# FPGA_Config.net
KiCad netlist of a schematic drawn in Altium Designer
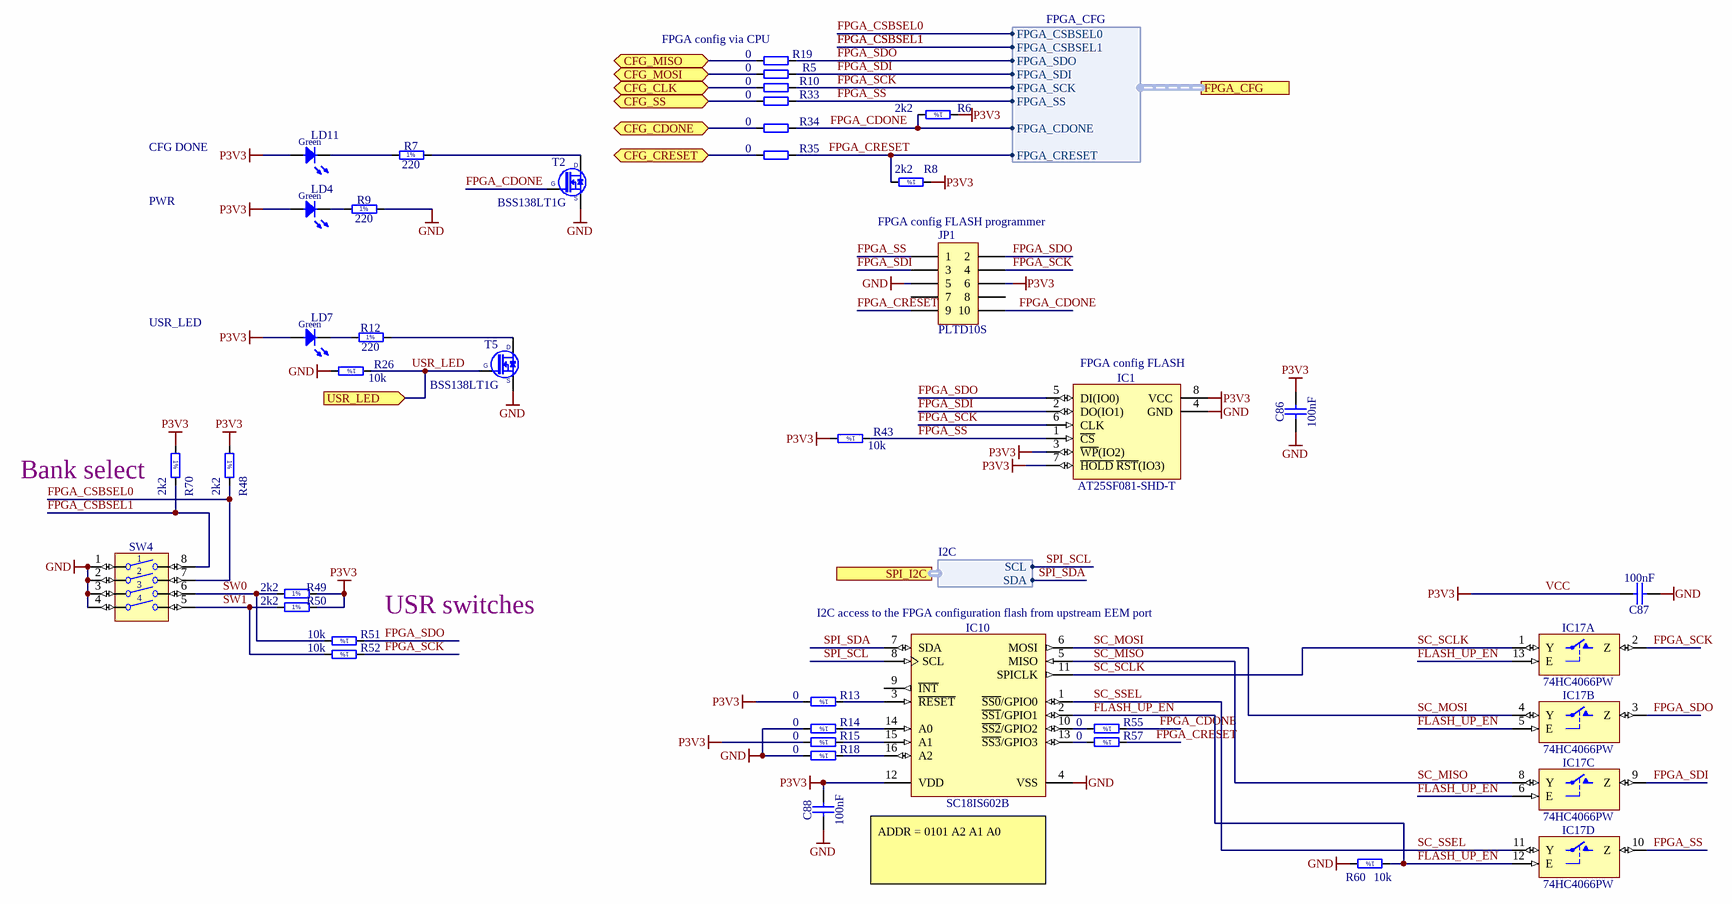
[diagram p0: FPGA_Config.SchDoc]

(export (version "E")
  (design (tool "Eeschema 10.0.6"))
  (components
    (comp (ref "C86")
      (value "100nF")
      (footprint "CAPC1005X55N")
      (description "Non-polarised capacitor")
      (fields
        (field (name "PART NUMBER") "CC0402_100NF_16V_10%_X5R")
        (field (name "VOLTAGE") "16V")
        (field (name "AUTHOR") "CERN DEM JLC")
      )
      (libsource (lib "Capacitors") (part "Capacitor - non polarized"))
    )
    (comp (ref "C87")
      (value "100nF")
      (footprint "CAPC1005X55N")
      (description "Non-polarised capacitor")
      (fields
        (field (name "PART NUMBER") "CC0402_100NF_16V_10%_X5R")
        (field (name "VOLTAGE") "16V")
        (field (name "AUTHOR") "CERN DEM JLC")
      )
      (libsource (lib "Capacitors") (part "Capacitor - non polarized"))
    )
    (comp (ref "C88")
      (value "100nF")
      (footprint "CAPC1005X55N")
      (description "Non-polarised capacitor")
      (fields
        (field (name "PART NUMBER") "CC0402_100NF_16V_10%_X5R")
        (field (name "VOLTAGE") "16V")
        (field (name "AUTHOR") "CERN DEM JLC")
      )
      (libsource (lib "Capacitors") (part "Capacitor - non polarized"))
    )
    (comp (ref "IC1")
      (value "AT25SF081-SHD-T")
      (footprint "SOIC127P790X216-8N")
      (description "8M-bit Serial Flash Memory with uniform 4KB sectors and Dual/Quad SPI and QPI")
      (fields (field (name "MANUFACTURER") "ADESTO") (field (name "AUTHOR") "GK"))
      (libsource (lib "LIBRARY_SCH") (part "MEM_AT25SF081-SHD-T"))
    )
    (comp (ref "IC10")
      (value "SC18IS602B")
      (footprint "SOP65P640X110-16N")
      (description "I2C-bus to SPI bridge")
      (fields (field (name "MANUFACTURER") "NXP SEMICONDUCTORS") (field (name "AUTHOR") "CERN DEM MR"))
      (libsource (lib "ICs And Semiconductors") (part "SC18IS602B"))
    )
    (comp (ref "IC17")
      (value "74HC4066PW")
      (footprint "SOP65P640X110-14N")
      (fields (field (name "MANUFACTURER") "NXP SEMICONDUCTORS") (field (name "AUTHOR") "CERN DEM JLC"))
      (libsource (lib "ICs And Semiconductors") (part "4066"))
    )
    (comp (ref "JP1")
      (value "PLTD10S")
      (footprint "PLTD10S")
      (description "Goldpin 2.54mm, male header")
      (libsource (lib "LIBRARY_SCH") (part "CON_2x5 2.54 male SMT"))
    )
    (comp (ref "LD4")
      (value "Green")
      (footprint "LED_AVAGO_HSME-C120")
      (description "LED Green 1C 2A")
      (fields
        (field (name "PART NUMBER") "LED_AVAGO_HSME-C120")
        (field (name "MANUFACTURER") "AVAGO TECHNOLOGIES")
        (field (name "AUTHOR") "CERN DEM JMW")
      )
      (libsource (lib "ICs And Semiconductors") (part "LED Green 1C 2A"))
    )
    (comp (ref "LD7")
      (value "Green")
      (footprint "LED_AVAGO_HSME-C120")
      (description "LED Green 1C 2A")
      (fields
        (field (name "PART NUMBER") "LED_AVAGO_HSME-C120")
        (field (name "MANUFACTURER") "AVAGO TECHNOLOGIES")
        (field (name "AUTHOR") "CERN DEM JMW")
      )
      (libsource (lib "ICs And Semiconductors") (part "LED Green 1C 2A"))
    )
    (comp (ref "LD11")
      (value "Green")
      (footprint "LED_AVAGO_HSME-C120")
      (description "LED Green 1C 2A")
      (fields
        (field (name "PART NUMBER") "LED_AVAGO_HSME-C120")
        (field (name "MANUFACTURER") "AVAGO TECHNOLOGIES")
        (field (name "AUTHOR") "CERN DEM JMW")
      )
      (libsource (lib "ICs And Semiconductors") (part "LED Green 1C 2A"))
    )
    (comp (ref "R5")
      (value "0")
      (footprint "RESC1608X55N")
      (description "Resistor")
      (fields
        (field (name "PART NUMBER") "R0603_0R_JUMPER")
        (field (name "MANUFACTURER") "GENERIC")
        (field (name "AUTHOR") "CERN DEM JLC")
      )
      (libsource (lib "Resistors") (part "Resistor"))
    )
    (comp (ref "R6")
      (value "2k2")
      (footprint "RESC1005X40N")
      (description "Resistor - 1%")
      (fields
        (field (name "PART NUMBER") "R0402_2K2_1%_0.0625W_100PPM")
        (field (name "POWER") "0.0625W")
        (field (name "AUTHOR") "CERN DEM JLC")
      )
      (libsource (lib "Resistors") (part "Resistor - 1%"))
    )
    (comp (ref "R7")
      (value "220")
      (footprint "RESC1608X55N")
      (description "Resistor - 1%")
      (fields
        (field (name "PART NUMBER") "R0603_220R_1%_0.1W_100PPM")
        (field (name "POWER") "0.1W")
        (field (name "AUTHOR") "CERN DEM JLC")
      )
      (libsource (lib "Resistors") (part "Resistor - 1%"))
    )
    (comp (ref "R8")
      (value "2k2")
      (footprint "RESC1005X40N")
      (description "Resistor - 1%")
      (fields
        (field (name "PART NUMBER") "R0402_2K2_1%_0.0625W_100PPM")
        (field (name "POWER") "0.0625W")
        (field (name "AUTHOR") "CERN DEM JLC")
      )
      (libsource (lib "Resistors") (part "Resistor - 1%"))
    )
    (comp (ref "R9")
      (value "220")
      (footprint "RESC1608X55N")
      (description "Resistor - 1%")
      (fields
        (field (name "PART NUMBER") "R0603_220R_1%_0.1W_100PPM")
        (field (name "POWER") "0.1W")
        (field (name "AUTHOR") "CERN DEM JLC")
      )
      (libsource (lib "Resistors") (part "Resistor - 1%"))
    )
    (comp (ref "R10")
      (value "0")
      (footprint "RESC1608X55N")
      (description "Resistor")
      (fields
        (field (name "PART NUMBER") "R0603_0R_JUMPER")
        (field (name "MANUFACTURER") "GENERIC")
        (field (name "AUTHOR") "CERN DEM JLC")
      )
      (libsource (lib "Resistors") (part "Resistor"))
    )
    (comp (ref "R12")
      (value "220")
      (footprint "RESC1608X55N")
      (description "Resistor - 1%")
      (fields
        (field (name "PART NUMBER") "R0603_220R_1%_0.1W_100PPM")
        (field (name "POWER") "0.1W")
        (field (name "AUTHOR") "CERN DEM JLC")
      )
      (libsource (lib "Resistors") (part "Resistor - 1%"))
    )
    (comp (ref "R13")
      (value "0")
      (footprint "RESC1608X55N")
      (description "Resistor - 1%")
      (fields
        (field (name "PART NUMBER") "R0603_0R_JUMPER")
        (field (name "MANUFACTURER") "GENERIC")
        (field (name "AUTHOR") "CERN DEM JLC")
      )
      (libsource (lib "Resistors") (part "Resistor - 1%"))
    )
    (comp (ref "R14")
      (value "0")
      (footprint "RESC1608X55N")
      (description "Resistor - 1%")
      (fields
        (field (name "PART NUMBER") "R0603_0R_JUMPER")
        (field (name "MANUFACTURER") "GENERIC")
        (field (name "AUTHOR") "CERN DEM JLC")
      )
      (libsource (lib "Resistors") (part "Resistor - 1%"))
    )
    (comp (ref "R15")
      (value "0")
      (footprint "RESC1608X55N")
      (description "Resistor - 1%")
      (fields
        (field (name "PART NUMBER") "R0603_0R_JUMPER")
        (field (name "MANUFACTURER") "GENERIC")
        (field (name "AUTHOR") "CERN DEM JLC")
      )
      (libsource (lib "Resistors") (part "Resistor - 1%"))
    )
    (comp (ref "R18")
      (value "0")
      (footprint "RESC1608X55N")
      (description "Resistor - 1%")
      (fields
        (field (name "PART NUMBER") "R0603_0R_JUMPER")
        (field (name "MANUFACTURER") "GENERIC")
        (field (name "AUTHOR") "CERN DEM JLC")
      )
      (libsource (lib "Resistors") (part "Resistor - 1%"))
    )
    (comp (ref "R19")
      (value "0")
      (footprint "RESC1608X55N")
      (description "Resistor")
      (fields
        (field (name "PART NUMBER") "R0603_0R_JUMPER")
        (field (name "MANUFACTURER") "GENERIC")
        (field (name "AUTHOR") "CERN DEM JLC")
      )
      (libsource (lib "Resistors") (part "Resistor"))
    )
    (comp (ref "R26")
      (value "10k")
      (footprint "RESC1005X40N")
      (description "Resistor - 1%")
      (fields
        (field (name "PART NUMBER") "R0402_10K_1%_0.0625W_100PPM")
        (field (name "POWER") "0.0625W")
        (field (name "AUTHOR") "CERN DEM JLC")
      )
      (libsource (lib "Resistors") (part "Resistor - 1%"))
    )
    (comp (ref "R33")
      (value "0")
      (footprint "RESC1608X55N")
      (description "Resistor")
      (fields
        (field (name "PART NUMBER") "R0603_0R_JUMPER")
        (field (name "MANUFACTURER") "GENERIC")
        (field (name "AUTHOR") "CERN DEM JLC")
      )
      (libsource (lib "Resistors") (part "Resistor"))
    )
    (comp (ref "R34")
      (value "0")
      (footprint "RESC1608X55N")
      (description "Resistor")
      (fields
        (field (name "PART NUMBER") "R0603_0R_JUMPER")
        (field (name "MANUFACTURER") "GENERIC")
        (field (name "AUTHOR") "CERN DEM JLC")
      )
      (libsource (lib "Resistors") (part "Resistor"))
    )
    (comp (ref "R35")
      (value "0")
      (footprint "RESC1608X55N")
      (description "Resistor")
      (fields
        (field (name "PART NUMBER") "R0603_0R_JUMPER")
        (field (name "MANUFACTURER") "GENERIC")
        (field (name "AUTHOR") "CERN DEM JLC")
      )
      (libsource (lib "Resistors") (part "Resistor"))
    )
    (comp (ref "R43")
      (value "10k")
      (footprint "RESC1005X40N")
      (description "Resistor - 1%")
      (fields
        (field (name "PART NUMBER") "R0402_10K_1%_0.0625W_100PPM")
        (field (name "POWER") "0.0625W")
        (field (name "AUTHOR") "CERN DEM JLC")
      )
      (libsource (lib "Resistors") (part "Resistor - 1%"))
    )
    (comp (ref "R48")
      (value "2k2")
      (footprint "RESC1005X40N")
      (description "Resistor - 1%")
      (fields
        (field (name "PART NUMBER") "R0402_2K2_1%_0.0625W_100PPM")
        (field (name "POWER") "0.0625W")
        (field (name "AUTHOR") "CERN DEM JLC")
      )
      (libsource (lib "Resistors") (part "Resistor - 1%"))
    )
    (comp (ref "R49")
      (value "2k2")
      (footprint "RESC1005X40N")
      (description "Resistor - 1%")
      (fields
        (field (name "PART NUMBER") "R0402_2K2_1%_0.0625W_100PPM")
        (field (name "POWER") "0.0625W")
        (field (name "AUTHOR") "CERN DEM JLC")
      )
      (libsource (lib "Resistors") (part "Resistor - 1%"))
    )
    (comp (ref "R50")
      (value "2k2")
      (footprint "RESC1005X40N")
      (description "Resistor - 1%")
      (fields
        (field (name "PART NUMBER") "R0402_2K2_1%_0.0625W_100PPM")
        (field (name "POWER") "0.0625W")
        (field (name "AUTHOR") "CERN DEM JLC")
      )
      (libsource (lib "Resistors") (part "Resistor - 1%"))
    )
    (comp (ref "R51")
      (value "10k")
      (footprint "RESC1005X40N")
      (description "Resistor - 1%")
      (fields
        (field (name "PART NUMBER") "R0402_10K_1%_0.0625W_100PPM")
        (field (name "POWER") "0.0625W")
        (field (name "AUTHOR") "CERN DEM JLC")
      )
      (libsource (lib "Resistors") (part "Resistor - 1%"))
    )
    (comp (ref "R52")
      (value "10k")
      (footprint "RESC1005X40N")
      (description "Resistor - 1%")
      (fields
        (field (name "PART NUMBER") "R0402_10K_1%_0.0625W_100PPM")
        (field (name "POWER") "0.0625W")
        (field (name "AUTHOR") "CERN DEM JLC")
      )
      (libsource (lib "Resistors") (part "Resistor - 1%"))
    )
    (comp (ref "R55")
      (value "0")
      (footprint "RESC1608X55N")
      (description "Resistor - 1%")
      (fields
        (field (name "PART NUMBER") "R0603_0R_JUMPER")
        (field (name "MANUFACTURER") "GENERIC")
        (field (name "AUTHOR") "CERN DEM JLC")
      )
      (libsource (lib "Resistors") (part "Resistor - 1%"))
    )
    (comp (ref "R57")
      (value "0")
      (footprint "RESC1608X55N")
      (description "Resistor - 1%")
      (fields
        (field (name "PART NUMBER") "R0603_0R_JUMPER")
        (field (name "MANUFACTURER") "GENERIC")
        (field (name "AUTHOR") "CERN DEM JLC")
      )
      (libsource (lib "Resistors") (part "Resistor - 1%"))
    )
    (comp (ref "R60")
      (value "10k")
      (footprint "RESC1005X40N")
      (description "Resistor - 1%")
      (fields
        (field (name "PART NUMBER") "R0402_10K_1%_0.0625W_100PPM")
        (field (name "POWER") "0.0625W")
        (field (name "AUTHOR") "CERN DEM JLC")
      )
      (libsource (lib "Resistors") (part "Resistor - 1%"))
    )
    (comp (ref "R70")
      (value "2k2")
      (footprint "RESC1005X40N")
      (description "Resistor - 1%")
      (fields
        (field (name "PART NUMBER") "R0402_2K2_1%_0.0625W_100PPM")
        (field (name "POWER") "0.0625W")
        (field (name "AUTHOR") "CERN DEM JLC")
      )
      (libsource (lib "Resistors") (part "Resistor - 1%"))
    )
    (comp (ref "SW4")
      (value "Switch")
      (footprint "SW_TYCO_1571983-4")
      (description "4 Ways SPST DIP Switch")
      (fields
        (field (name "PART NUMBER") "SW_TYCO_1571983-4")
        (field (name "MANUFACTURER") "TYCO")
        (field (name "AUTHOR") "CERN DEM JLC")
      )
      (libsource (lib "Eletro-mechanical") (part "SW 4x SPST DIP Switch"))
    )
    (comp (ref "T2")
      (value "BSS138LT1G")
      (footprint "SOT95P240X110-3N")
      (description "N-CHANNEL MOSFET WITH DIODE")
      (fields (field (name "MANUFACTURER") "ON SEMICONDUCTOR") (field (name "AUTHOR") "CERN DEM JLC"))
      (libsource (lib "ICs And Semiconductors") (part "N-MOSFET-D 1G 2S 3D"))
    )
    (comp (ref "T5")
      (value "BSS138LT1G")
      (footprint "SOT95P240X110-3N")
      (description "N-CHANNEL MOSFET WITH DIODE")
      (fields (field (name "MANUFACTURER") "ON SEMICONDUCTOR") (field (name "AUTHOR") "CERN DEM JLC"))
      (libsource (lib "ICs And Semiconductors") (part "N-MOSFET-D 1G 2S 3D"))
    )
  )
  (nets
    (net (code "3") (name "/CFG_CDONE") (class "Default")
      (node (ref "R34") (pin "1") (pinfunction "1_1") (pintype "passive"))
    )
    (net (code "4") (name "/CFG_CLK") (class "Default")
      (node (ref "R10") (pin "1") (pinfunction "1_1") (pintype "passive"))
    )
    (net (code "5") (name "/CFG_CRESET") (class "Default")
      (node (ref "R35") (pin "1") (pinfunction "1_1") (pintype "passive"))
    )
    (net (code "6") (name "/CFG_MISO") (class "Default")
      (node (ref "R19") (pin "1") (pinfunction "1_1") (pintype "passive"))
    )
    (net (code "7") (name "/CFG_MOSI") (class "Default")
      (node (ref "R5") (pin "1") (pinfunction "1_1") (pintype "passive"))
    )
    (net (code "8") (name "/CFG_SS") (class "Default")
      (node (ref "R33") (pin "1") (pinfunction "1_1") (pintype "passive"))
    )
    (net (code "9") (name "/FLASH_UP_EN") (class "Default")
      (node (ref "IC10") (pin "2") (pinfunction "~{SS1}/GPIO1_2") (pintype "bidirectional"))
      (node (ref "IC17") (pin "12") (pinfunction "E_12") (pintype "input"))
      (node (ref "IC17") (pin "13") (pinfunction "E_13") (pintype "input"))
      (node (ref "IC17") (pin "5") (pinfunction "E_5") (pintype "input"))
      (node (ref "IC17") (pin "6") (pinfunction "E_6") (pintype "input"))
      (node (ref "R60") (pin "1") (pinfunction "1_1") (pintype "passive"))
    )
    (net (code "10") (name "/FPGA_CDONE") (class "Default")
      (node (ref "JP1") (pin "10") (pinfunction "10_10") (pintype "passive"))
      (node (ref "R34") (pin "2") (pinfunction "2_2") (pintype "passive"))
      (node (ref "R55") (pin "1") (pinfunction "1_1") (pintype "passive"))
      (node (ref "R6") (pin "2") (pinfunction "2_2") (pintype "passive"))
      (node (ref "T2") (pin "1") (pinfunction "G_1") (pintype "passive"))
    )
    (net (code "11") (name "/FPGA_CRESET") (class "Default")
      (node (ref "JP1") (pin "9") (pinfunction "9_9") (pintype "passive"))
      (node (ref "R35") (pin "2") (pinfunction "2_2") (pintype "passive"))
      (node (ref "R57") (pin "1") (pinfunction "1_1") (pintype "passive"))
      (node (ref "R8") (pin "2") (pinfunction "2_2") (pintype "passive"))
    )
    (net (code "12") (name "/FPGA_CSBSEL0") (class "Default")
      (node (ref "R48") (pin "2") (pinfunction "2_2") (pintype "passive"))
      (node (ref "SW4") (pin "7") (pinfunction "7_7") (pintype "bidirectional"))
    )
    (net (code "13") (name "/FPGA_CSBSEL1") (class "Default")
      (node (ref "R70") (pin "2") (pinfunction "2_2") (pintype "passive"))
      (node (ref "SW4") (pin "8") (pinfunction "8_8") (pintype "bidirectional"))
    )
    (net (code "14") (name "/FPGA_SCK") (class "Default")
      (node (ref "IC1") (pin "6") (pinfunction "CLK_6") (pintype "input"))
      (node (ref "IC17") (pin "2") (pinfunction "Z_2") (pintype "bidirectional"))
      (node (ref "JP1") (pin "4") (pinfunction "4_4") (pintype "passive"))
      (node (ref "R10") (pin "2") (pinfunction "2_2") (pintype "passive"))
      (node (ref "R52") (pin "1") (pinfunction "1_1") (pintype "passive"))
    )
    (net (code "15") (name "/FPGA_SDI") (class "Default")
      (node (ref "IC1") (pin "2") (pinfunction "DO(IO1)_2") (pintype "bidirectional"))
      (node (ref "IC17") (pin "9") (pinfunction "Z_9") (pintype "bidirectional"))
      (node (ref "JP1") (pin "3") (pinfunction "3_3") (pintype "passive"))
      (node (ref "R5") (pin "2") (pinfunction "2_2") (pintype "passive"))
    )
    (net (code "16") (name "/FPGA_SDO") (class "Default")
      (node (ref "IC1") (pin "5") (pinfunction "DI(IO0)_5") (pintype "bidirectional"))
      (node (ref "IC17") (pin "3") (pinfunction "Z_3") (pintype "bidirectional"))
      (node (ref "JP1") (pin "2") (pinfunction "2_2") (pintype "passive"))
      (node (ref "R19") (pin "2") (pinfunction "2_2") (pintype "passive"))
      (node (ref "R51") (pin "1") (pinfunction "1_1") (pintype "passive"))
    )
    (net (code "17") (name "/FPGA_SS") (class "Default")
      (node (ref "IC1") (pin "1") (pinfunction "~{CS}_1") (pintype "input"))
      (node (ref "IC17") (pin "10") (pinfunction "Z_10") (pintype "bidirectional"))
      (node (ref "JP1") (pin "1") (pinfunction "1_1") (pintype "passive"))
      (node (ref "R33") (pin "2") (pinfunction "2_2") (pintype "passive"))
      (node (ref "R43") (pin "1") (pinfunction "1_1") (pintype "passive"))
    )
    (net (code "18") (name "/SC_MISO") (class "Default")
      (node (ref "IC10") (pin "5") (pinfunction "MISO_5") (pintype "input"))
      (node (ref "IC17") (pin "8") (pinfunction "Y_8") (pintype "bidirectional"))
    )
    (net (code "19") (name "/SC_MOSI") (class "Default")
      (node (ref "IC10") (pin "6") (pinfunction "MOSI_6") (pintype "output"))
      (node (ref "IC17") (pin "4") (pinfunction "Y_4") (pintype "bidirectional"))
    )
    (net (code "20") (name "/SC_SCLK") (class "Default")
      (node (ref "IC10") (pin "11") (pinfunction "SPICLK_11") (pintype "output"))
      (node (ref "IC17") (pin "1") (pinfunction "Y_1") (pintype "bidirectional"))
    )
    (net (code "21") (name "/SC_SSEL") (class "Default")
      (node (ref "IC10") (pin "1") (pinfunction "~{SS0}/GPIO0_1") (pintype "bidirectional"))
      (node (ref "IC17") (pin "11") (pinfunction "Y_11") (pintype "bidirectional"))
    )
    (net (code "22") (name "/SPI_SCL") (class "Default")
      (node (ref "IC10") (pin "8") (pinfunction "SCL_8") (pintype "input"))
    )
    (net (code "23") (name "/SPI_SDA") (class "Default")
      (node (ref "IC10") (pin "7") (pinfunction "SDA_7") (pintype "bidirectional"))
    )
    (net (code "24") (name "/SW0") (class "Default")
      (node (ref "R49") (pin "1") (pinfunction "1_1") (pintype "passive"))
      (node (ref "R51") (pin "2") (pinfunction "2_2") (pintype "passive"))
      (node (ref "SW4") (pin "6") (pinfunction "6_6") (pintype "bidirectional"))
    )
    (net (code "25") (name "/SW1") (class "Default")
      (node (ref "R50") (pin "1") (pinfunction "1_1") (pintype "passive"))
      (node (ref "R52") (pin "2") (pinfunction "2_2") (pintype "passive"))
      (node (ref "SW4") (pin "5") (pinfunction "5_5") (pintype "bidirectional"))
    )
    (net (code "26") (name "/USR_LED") (class "Default")
      (node (ref "R26") (pin "1") (pinfunction "1_1") (pintype "passive"))
      (node (ref "T5") (pin "1") (pinfunction "G_1") (pintype "passive"))
    )
    (net (code "29") (name "GND") (class "Default")
      (node (ref "C86") (pin "1") (pinfunction "1_1") (pintype "passive"))
      (node (ref "C87") (pin "1") (pinfunction "1_1") (pintype "passive"))
      (node (ref "C88") (pin "1") (pinfunction "1_1") (pintype "passive"))
      (node (ref "IC1") (pin "4") (pinfunction "GND_4") (pintype "power_in"))
      (node (ref "IC10") (pin "4") (pinfunction "VSS_4") (pintype "power_in"))
      (node (ref "IC17") (pin "7") (pinfunction "GND_7") (pintype "power_in"))
      (node (ref "JP1") (pin "5") (pinfunction "5_5") (pintype "passive"))
      (node (ref "R14") (pin "2") (pinfunction "2_2") (pintype "passive"))
      (node (ref "R18") (pin "2") (pinfunction "2_2") (pintype "passive"))
      (node (ref "R26") (pin "2") (pinfunction "2_2") (pintype "passive"))
      (node (ref "R60") (pin "2") (pinfunction "2_2") (pintype "passive"))
      (node (ref "R9") (pin "2") (pinfunction "2_2") (pintype "passive"))
      (node (ref "SW4") (pin "1") (pinfunction "1_1") (pintype "bidirectional"))
      (node (ref "SW4") (pin "2") (pinfunction "2_2") (pintype "bidirectional"))
      (node (ref "SW4") (pin "3") (pinfunction "3_3") (pintype "bidirectional"))
      (node (ref "SW4") (pin "4") (pinfunction "4_4") (pintype "bidirectional"))
      (node (ref "T2") (pin "2") (pinfunction "S_2") (pintype "passive"))
      (node (ref "T5") (pin "2") (pinfunction "S_2") (pintype "passive"))
    )
    (net (code "30") (name "Net-(IC10-A0)") (class "Default")
      (node (ref "IC10") (pin "14") (pinfunction "A0_14") (pintype "input"))
      (node (ref "R14") (pin "1") (pinfunction "1_1") (pintype "passive"))
    )
    (net (code "31") (name "Net-(IC10-A1)") (class "Default")
      (node (ref "IC10") (pin "15") (pinfunction "A1_15") (pintype "input"))
      (node (ref "R15") (pin "1") (pinfunction "1_1") (pintype "passive"))
    )
    (net (code "32") (name "Net-(IC10-A2)") (class "Default")
      (node (ref "IC10") (pin "16") (pinfunction "A2_16") (pintype "bidirectional"))
      (node (ref "R18") (pin "1") (pinfunction "1_1") (pintype "passive"))
    )
    (net (code "33") (name "Net-(IC10-~{RESET})") (class "Default")
      (node (ref "IC10") (pin "3") (pinfunction "~{RESET}_3") (pintype "input"))
      (node (ref "R13") (pin "1") (pinfunction "1_1") (pintype "passive"))
    )
    (net (code "34") (name "Net-(IC10-~{SS2}{slash}GPIO2)") (class "Default")
      (node (ref "IC10") (pin "10") (pinfunction "~{SS2}/GPIO2_10") (pintype "bidirectional"))
      (node (ref "R55") (pin "2") (pinfunction "2_2") (pintype "passive"))
    )
    (net (code "35") (name "Net-(IC10-~{SS3}{slash}GPIO3)") (class "Default")
      (node (ref "IC10") (pin "13") (pinfunction "~{SS3}/GPIO3_13") (pintype "bidirectional"))
      (node (ref "R57") (pin "2") (pinfunction "2_2") (pintype "passive"))
    )
    (net (code "36") (name "Net-(LD4-C)") (class "Default")
      (node (ref "LD4") (pin "1") (pinfunction "C_1") (pintype "passive"))
      (node (ref "R9") (pin "1") (pinfunction "1_1") (pintype "passive"))
    )
    (net (code "37") (name "Net-(LD7-C)") (class "Default")
      (node (ref "LD7") (pin "1") (pinfunction "C_1") (pintype "passive"))
      (node (ref "R12") (pin "1") (pinfunction "1_1") (pintype "passive"))
    )
    (net (code "38") (name "Net-(LD11-C)") (class "Default")
      (node (ref "LD11") (pin "1") (pinfunction "C_1") (pintype "passive"))
      (node (ref "R7") (pin "1") (pinfunction "1_1") (pintype "passive"))
    )
    (net (code "39") (name "Net-(T2-D)") (class "Default")
      (node (ref "R7") (pin "2") (pinfunction "2_2") (pintype "passive"))
      (node (ref "T2") (pin "3") (pinfunction "D_3") (pintype "passive"))
    )
    (net (code "40") (name "Net-(T5-D)") (class "Default")
      (node (ref "R12") (pin "2") (pinfunction "2_2") (pintype "passive"))
      (node (ref "T5") (pin "3") (pinfunction "D_3") (pintype "passive"))
    )
    (net (code "41") (name "P3V3") (class "Default")
      (node (ref "C86") (pin "2") (pinfunction "2_2") (pintype "passive"))
      (node (ref "C87") (pin "2") (pinfunction "2_2") (pintype "passive"))
      (node (ref "C88") (pin "2") (pinfunction "2_2") (pintype "passive"))
      (node (ref "IC1") (pin "3") (pinfunction "~{WP}(IO2)_3") (pintype "bidirectional"))
      (node (ref "IC1") (pin "7") (pinfunction "~{HOLD}_~{RST}(IO3)_7") (pintype "bidirectional"))
      (node (ref "IC1") (pin "8") (pinfunction "VCC_8") (pintype "power_in"))
      (node (ref "IC10") (pin "12") (pinfunction "VDD_12") (pintype "power_in"))
      (node (ref "IC17") (pin "14") (pinfunction "VCC_14") (pintype "power_in"))
      (node (ref "JP1") (pin "6") (pinfunction "6_6") (pintype "passive"))
      (node (ref "LD11") (pin "2") (pinfunction "A_2") (pintype "passive"))
      (node (ref "LD4") (pin "2") (pinfunction "A_2") (pintype "passive"))
      (node (ref "LD7") (pin "2") (pinfunction "A_2") (pintype "passive"))
      (node (ref "R13") (pin "2") (pinfunction "2_2") (pintype "passive"))
      (node (ref "R15") (pin "2") (pinfunction "2_2") (pintype "passive"))
      (node (ref "R43") (pin "2") (pinfunction "2_2") (pintype "passive"))
      (node (ref "R48") (pin "1") (pinfunction "1_1") (pintype "passive"))
      (node (ref "R49") (pin "2") (pinfunction "2_2") (pintype "passive"))
      (node (ref "R50") (pin "2") (pinfunction "2_2") (pintype "passive"))
      (node (ref "R6") (pin "1") (pinfunction "1_1") (pintype "passive"))
      (node (ref "R70") (pin "1") (pinfunction "1_1") (pintype "passive"))
      (node (ref "R8") (pin "1") (pinfunction "1_1") (pintype "passive"))
    )
    (net (code "42") (name "unconnected-(IC10-~{INT}-Pad9)") (class "Default")
      (node (ref "IC10") (pin "9") (pinfunction "~{INT}_9") (pintype "output"))
    )
    (net (code "43") (name "unconnected-(JP1-Pad7)") (class "Default")
      (node (ref "JP1") (pin "7") (pinfunction "7_7") (pintype "passive"))
    )
    (net (code "44") (name "unconnected-(JP1-Pad8)") (class "Default")
      (node (ref "JP1") (pin "8") (pinfunction "8_8") (pintype "passive"))
    )
  )
)
